# Schema_linksonder.net
KiCad netlist of a schematic drawn in Altium Designer
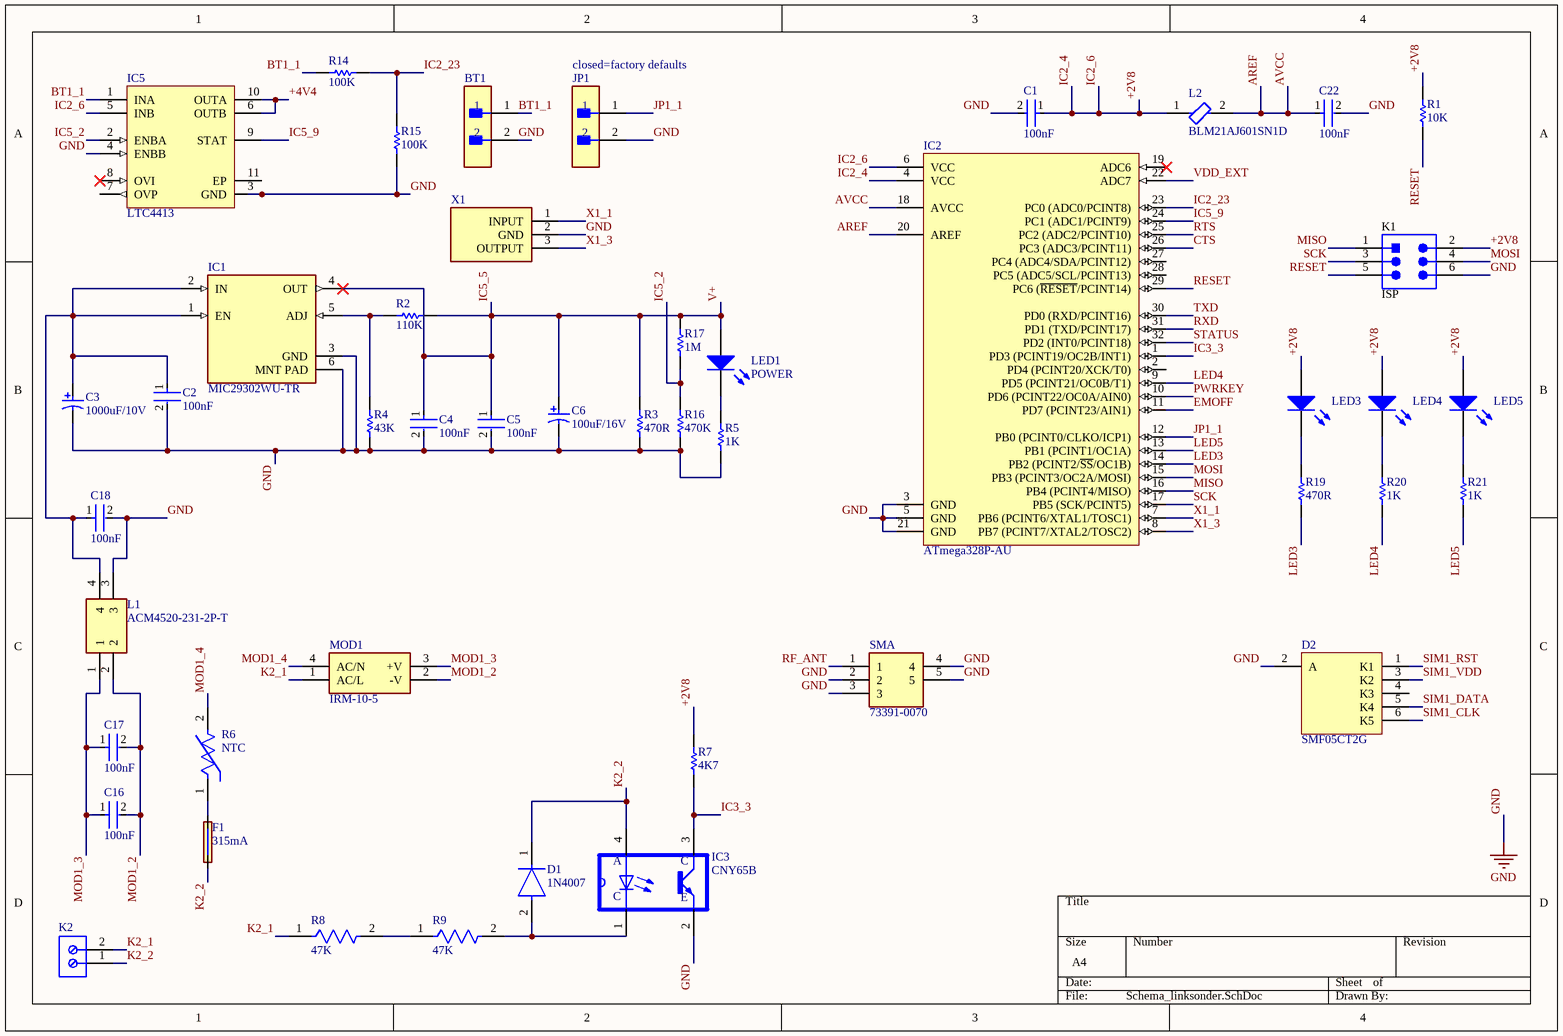
[diagram p0: Schema_linksonder.SchDoc]

(export (version "E")
  (design (tool "Eeschema 10.0.6"))
  (components
    (comp (ref "BT1")
      (value "~")
      (footprint "FP-M20-9990246-MFG")
      (description "CONN HEADER VERT 2POS 2.54MM")
      (fields
        (field (name "OCTOPART") "https://octopart.com/m20-9990246-harwin-2590635")
        (field (name "MANUFACTURER") "Harwin")
      )
      (libsource (lib "Altium Content Vault") (part "3bc925449376181038e59eaffc5286c"))
    )
    (comp (ref "C1")
      (value "100nF")
      (footprint "FP-CC1206-1_25-MFG")
      (description "CAP CER 0.1UF 50V X7R 1206")
      (fields
        (field (name "OCTOPART") "https://octopart.com/cc1206krx7r9bb104-yageo-39467816")
        (field (name "TOLERANCE") "0.1")
      )
      (libsource (lib "Altium Content Vault") (part "11868f565c42a9108669ba33697ecf6"))
    )
    (comp (ref "C2")
      (value "100nF")
      (footprint "FP-CC1206-1_25-MFG")
      (description "CAP CER 0.1UF 50V X7R 1206")
      (fields
        (field (name "OCTOPART") "https://octopart.com/cc1206krx7r9bb104-yageo-39467816")
        (field (name "TOLERANCE") "0.1")
      )
      (libsource (lib "Altium Content Vault") (part "11868f565c42a9108669ba33697ecf6"))
    )
    (comp (ref "C3")
      (value "1000uF/10V")
      (footprint "NIC-CAPA2-10X10_V")
      (fields (field (name "MANUFACTURER") "Nichicon") (field (name "PARTNUMBER") "UUD1A102MNL1GS"))
      (libsource (lib "Altium Content Vault") (part "NIC-CAP-P-2"))
    )
    (comp (ref "C4")
      (value "100nF")
      (footprint "FP-CC1206-1_25-MFG")
      (description "CAP CER 0.1UF 50V X7R 1206")
      (fields
        (field (name "OCTOPART") "https://octopart.com/cc1206krx7r9bb104-yageo-39467816")
        (field (name "TOLERANCE") "0.1")
      )
      (libsource (lib "Altium Content Vault") (part "11868f565c42a9108669ba33697ecf6"))
    )
    (comp (ref "C5")
      (value "100nF")
      (footprint "FP-CC1206-1_25-MFG")
      (description "CAP CER 0.1UF 50V X7R 1206")
      (fields
        (field (name "OCTOPART") "https://octopart.com/cc1206krx7r9bb104-yageo-39467816")
        (field (name "TOLERANCE") "0.1")
      )
      (libsource (lib "Altium Content Vault") (part "11868f565c42a9108669ba33697ecf6"))
    )
    (comp (ref "C6")
      (value "100uF/16V")
      (footprint "AVX-TAJ-C-2_M")
      (description "Standard Tantalum, 100 uF, +/- 10%, 16 V, -55 to 125 degC, 2-Pin SMD (2312), RoHS, Tape and Reel")
      (fields (field (name "TOLERANCE") "10%") (field (name "MANUFACTURER") "AVX"))
      (libsource (lib "Altium Content Vault") (part "CAP-P-2"))
    )
    (comp (ref "C16")
      (value "100nF")
      (footprint "FP-CC1206-1_25-MFG")
      (description "CAP CER 0.1UF 50V X7R 1206")
      (fields
        (field (name "OCTOPART") "https://octopart.com/cc1206krx7r9bb104-yageo-39467816")
        (field (name "TOLERANCE") "0.1")
      )
      (libsource (lib "Altium Content Vault") (part "11868f565c42a9108669ba33697ecf6"))
    )
    (comp (ref "C17")
      (value "100nF")
      (footprint "FP-CC1206-1_25-MFG")
      (description "CAP CER 0.1UF 50V X7R 1206")
      (fields
        (field (name "OCTOPART") "https://octopart.com/cc1206krx7r9bb104-yageo-39467816")
        (field (name "TOLERANCE") "0.1")
      )
      (libsource (lib "Altium Content Vault") (part "11868f565c42a9108669ba33697ecf6"))
    )
    (comp (ref "C18")
      (value "100nF")
      (footprint "FP-CC1206-1_25-MFG")
      (description "CAP CER 0.1UF 50V X7R 1206")
      (fields
        (field (name "OCTOPART") "https://octopart.com/cc1206krx7r9bb104-yageo-39467816")
        (field (name "TOLERANCE") "0.1")
      )
      (libsource (lib "Altium Content Vault") (part "11868f565c42a9108669ba33697ecf6"))
    )
    (comp (ref "C22")
      (value "100nF")
      (footprint "FP-CC1206-1_25-MFG")
      (description "CAP CER 0.1UF 50V X7R 1206")
      (fields
        (field (name "OCTOPART") "https://octopart.com/cc1206krx7r9bb104-yageo-39467816")
        (field (name "TOLERANCE") "0.1")
      )
      (libsource (lib "Altium Content Vault") (part "11868f565c42a9108669ba33697ecf6"))
    )
    (comp (ref "D1")
      (value "1N4007")
      (footprint "FP-1N4007-MFG")
      (description "DIODE GEN PURP 1KV 1A DO204AL")
      (fields
        (field (name "OCTOPART") "https://octopart.com/1n4007-e3%2F54-vishay-39548207")
        (field (name "MANUFACTURER") "Vishay")
      )
      (libsource (lib "Altium Content Vault") (part "d7152d700b627762746794eb795d46e"))
    )
    (comp (ref "D2")
      (value "SMF05CT2G")
      (footprint "ONSC-SC70-6-419B-02_W_V")
      (description "5-Line Transient Voltage Suppressor Array, 6-Pin SC70, Pb-Free, Tape and Reel")
      (fields (field (name "MANUFACTURER") "On Semiconductor"))
      (libsource (lib "Altium Content Vault") (part "ONSC-K1A2K3K4K5K6-6"))
    )
    (comp (ref "F1")
      (value "315mA")
      (footprint "MC000827")
      (description "Fuse Holder, 250 V, 6.3 A, Pcb Fuse Holder, Through Hole, 1")
      (fields (field (name "MF") "Multicomp") (field (name "MP") "MC000827"))
      (libsource (lib "MC000827") (part "MC000827"))
    )
    (comp (ref "IC1")
      (value "MIC29302WU-TR")
      (footprint "FP-C04-012-MFG")
      (description "IC REG LINEAR POS ADJ 3A TO263-5")
      (fields
        (field (name "MANUFACTURER") "Microchip")
        (field (name "OCTOPART") "https://octopart.com/mic29302wu-tr-microchip-66801318")
      )
      (libsource (lib "Altium Content Vault") (part "0db40f55fda0e91d0d14528974a446d"))
    )
    (comp (ref "IC2")
      (value "ATmega328P-AU")
      (footprint "32A_M")
      (libsource (lib "Altium Content Vault") (part "MC-8B-ATM48-SQ32"))
    )
    (comp (ref "IC3")
      (value "CNY65B")
      (footprint "DIP762W50P1524L1780H610Q4")
      (libsource (lib "CNY65B") (part "CNY65B"))
    )
    (comp (ref "IC5")
      (value "LTC4413")
      (footprint "LT-DD-10_V")
      (fields
        (field (name "MANUFACTURER") "Linear Technology")
        (field (name "PARTNUMBER") "LTC4413EDD-2#PBF")
      )
      (libsource (lib "Altium Content Vault") (part "LT-LTC4413-2-DD-10"))
    )
    (comp (ref "JP1")
      (value "closed=factory defaults")
      (footprint "FP-M20-9990246-MFG")
      (description "CONN HEADER VERT 2POS 2.54MM")
      (fields
        (field (name "OCTOPART") "https://octopart.com/m20-9990246-harwin-2590635")
        (field (name "MANUFACTURER") "Harwin")
      )
      (libsource (lib "Altium Content Vault") (part "3bc925449376181038e59eaffc5286c"))
    )
    (comp (ref "K1")
      (value "ISP")
      (footprint "SMTC-TSW-103-08-L-D_V")
      (fields (field (name "MANUFACTURER") "Samtec"))
      (libsource (lib "Altium Content Vault") (part "CN-2P-M-R6"))
    )
    (comp (ref "K2")
      (value "~")
      (footprint "PHOE-1714955_V")
      (description "PC Terminal Block, Pitch 6.35 mm, 1 x 2 Position, Height 21.5 mm, Tail Lenght 5.1 mm, RoHS, Bulk")
      (fields (field (name "MANUFACTURER") "Phoenix Contact"))
      (libsource (lib "Altium Content Vault") (part "CN-1P-F-TB2"))
    )
    (comp (ref "L1")
      (value "ACM4520-231-2P-T")
      (footprint "SamacSys:ACM4520")
      (description "Filter")
      (fields
        (field (name "RS PART NUMBER") "9164134P")
        (field (name "MANUFACTURER_PART_NUMBER") "ACM4520-231-2P-T000")
      )
      (libsource (lib "*") (part "ACM4520-231-2P-T000"))
    )
    (comp (ref "L2")
      (value "BLM21AJ601SN1D")
      (footprint "FP-BLM21-0_2-t0_85-e0_5-MFG")
      (description "Chip Ferrite Bead, 0805, 22Ω @ 100MHz, 0.009Ω, 25%, 6A")
      (fields (field (name "TOLERANCE") "25%"))
      (libsource (lib "Altium Content Vault") (part "5f30dd21d616792df468990f7003faa"))
    )
    (comp (ref "LED1")
      (value "POWER")
      (footprint "1206_A")
      (description "SMD mono-color Chip LED, WL-SMCW, Yellow")
      (fields (field (name "PARTNUMBER") "150120YS75000") (field (name "MANUFACTURER") "Wuerth Elektronik"))
      (libsource (lib "Altium Content Vault") (part "WE-LED_K1A2-2"))
    )
    (comp (ref "LED3")
      (value "~")
      (footprint "1206_A")
      (description "SMD mono-color Chip LED, WL-SMCW, Green")
      (fields (field (name "MANUFACTURER") "Wuerth Elektronik") (field (name "PARTNUMBER") "150120GS75000"))
      (libsource (lib "Altium Content Vault") (part "WE-LED_K1A2-2"))
    )
    (comp (ref "LED4")
      (value "~")
      (footprint "1206_A")
      (description "SMD mono-color Chip LED, WL-SMCW, Green")
      (fields (field (name "MANUFACTURER") "Wuerth Elektronik") (field (name "PARTNUMBER") "150120GS75000"))
      (libsource (lib "Altium Content Vault") (part "WE-LED_K1A2-2"))
    )
    (comp (ref "LED5")
      (value "~")
      (footprint "1206_A")
      (description "SMD mono-color Chip LED, WL-SMCW, Green")
      (fields (field (name "MANUFACTURER") "Wuerth Elektronik") (field (name "PARTNUMBER") "150120GS75000"))
      (libsource (lib "Altium Content Vault") (part "WE-LED_K1A2-2"))
    )
    (comp (ref "MOD1")
      (value "IRM-10-5")
      (footprint "SamacSys:IRM-10")
      (description "Power Supply")
      (fields (field (name "MOUSER PART NUMBER") "709-IRM10-5"))
      (libsource (lib "IRM-10-5") (part "IRM-10-5"))
    )
    (comp (ref "R1")
      (value "10K")
      (footprint "RESC3225X70X50NL20T20")
      (fields (field (name "MANUFACTURER") "Panasonic") (field (name "PART NUMBER") "ERJ14BQF3R3U"))
      (libsource (lib "Altium Content Vault") (part "RES"))
    )
    (comp (ref "R2")
      (value "110K")
      (footprint "RESC3225X70X50NL20T20")
      (fields (field (name "MANUFACTURER") "Panasonic") (field (name "PART NUMBER") "ERJ14BQF3R3U"))
      (libsource (lib "Altium Content Vault") (part "RES"))
    )
    (comp (ref "R3")
      (value "470R")
      (footprint "RESC3225X70X50NL20T20")
      (fields (field (name "MANUFACTURER") "Panasonic") (field (name "PART NUMBER") "ERJ14BQF3R3U"))
      (libsource (lib "Altium Content Vault") (part "RES"))
    )
    (comp (ref "R4")
      (value "43K")
      (footprint "RESC3225X70X50NL20T20")
      (fields (field (name "MANUFACTURER") "Panasonic") (field (name "PART NUMBER") "ERJ14BQF3R3U"))
      (libsource (lib "Altium Content Vault") (part "RES"))
    )
    (comp (ref "R5")
      (value "1K")
      (footprint "RESC3225X70X50NL20T20")
      (fields (field (name "MANUFACTURER") "Panasonic") (field (name "PART NUMBER") "ERJ14BQF3R3U"))
      (libsource (lib "Altium Content Vault") (part "RES"))
    )
    (comp (ref "R6")
      (value "NTC")
      (footprint "FP-NTPAA-MFG")
      (description "ICL 5.1 OHM 15% 2.5A 10MM")
      (fields (field (name "TOLERANCE") "15%") (field (name "VOLTAGE") "264V"))
      (libsource (lib "Altium Content Vault") (part "3b148a6ebabc5fb4d708a66c052d352"))
    )
    (comp (ref "R7")
      (value "4K7")
      (footprint "RESC3225X70X50NL20T20")
      (fields (field (name "MANUFACTURER") "Panasonic") (field (name "PART NUMBER") "ERJ14BQF3R3U"))
      (libsource (lib "Altium Content Vault") (part "RES"))
    )
    (comp (ref "R8")
      (value "47K")
      (footprint "FP-MRS25-MFG")
      (description "RES 1.1K OHM 0.6W 1% AXIAL")
      (fields
        (field (name "MANUFACTURER") "Vishay BC Components")
        (field (name "OCTOPART") "https://octopart.com/mrs25000c1101fct00-vishay-43740214")
      )
      (libsource (lib "Altium Content Vault") (part "1029c3af85768c4190bb7ad29bc67b5"))
    )
    (comp (ref "R9")
      (value "47K")
      (footprint "FP-MRS25-MFG")
      (description "RES 1.1K OHM 0.6W 1% AXIAL")
      (fields
        (field (name "MANUFACTURER") "Vishay BC Components")
        (field (name "OCTOPART") "https://octopart.com/mrs25000c1101fct00-vishay-43740214")
      )
      (libsource (lib "Altium Content Vault") (part "1029c3af85768c4190bb7ad29bc67b5"))
    )
    (comp (ref "R14")
      (value "100K")
      (footprint "RESC3225X70X50NL20T20")
      (fields (field (name "MANUFACTURER") "Panasonic") (field (name "PART NUMBER") "ERJ14BQF3R3U"))
      (libsource (lib "Altium Content Vault") (part "RES"))
    )
    (comp (ref "R15")
      (value "100K")
      (footprint "RESC3225X70X50NL20T20")
      (fields (field (name "MANUFACTURER") "Panasonic") (field (name "PART NUMBER") "ERJ14BQF3R3U"))
      (libsource (lib "Altium Content Vault") (part "RES"))
    )
    (comp (ref "R16")
      (value "470K")
      (footprint "RESC3225X70X50NL20T20")
      (fields (field (name "MANUFACTURER") "Panasonic") (field (name "PART NUMBER") "ERJ14BQF3R3U"))
      (libsource (lib "Altium Content Vault") (part "RES"))
    )
    (comp (ref "R17")
      (value "1M")
      (footprint "RESC3225X70X50NL20T20")
      (fields (field (name "MANUFACTURER") "Panasonic") (field (name "PART NUMBER") "ERJ14BQF3R3U"))
      (libsource (lib "Altium Content Vault") (part "RES"))
    )
    (comp (ref "R19")
      (value "470R")
      (footprint "RESC3225X70X50NL20T20")
      (fields (field (name "MANUFACTURER") "Panasonic") (field (name "PART NUMBER") "ERJ14BQF3R3U"))
      (libsource (lib "Altium Content Vault") (part "RES"))
    )
    (comp (ref "R20")
      (value "1K")
      (footprint "RESC3225X70X50NL20T20")
      (fields (field (name "MANUFACTURER") "Panasonic") (field (name "PART NUMBER") "ERJ14BQF3R3U"))
      (libsource (lib "Altium Content Vault") (part "RES"))
    )
    (comp (ref "R21")
      (value "1K")
      (footprint "RESC3225X70X50NL20T20")
      (fields (field (name "MANUFACTURER") "Panasonic") (field (name "PART NUMBER") "ERJ14BQF3R3U"))
      (libsource (lib "Altium Content Vault") (part "RES"))
    )
    (comp (ref "SMA")
      (value "73391-0070")
      (footprint "SamacSys:733910070")
      (description "Connector")
      (fields (field (name "MOUSER PART NUMBER") "538-73391-0070"))
      (libsource (lib "Molex 73391-0070") (part "73391-0070"))
    )
    (comp (ref "X1")
      (value "~")
      (footprint "SamacSys:CSTCC8M00G53R0")
      (description "Crystal or Oscillator")
      (fields
        (field (name "MANUFACTURER_PART_NUMBER") "CSTCC8M00G53-R0")
        (field (name "MOUSER PART NUMBER") "81-CSTCC8.00MG-TC")
      )
      (libsource (lib "*") (part "CSTCC8M00G53-R0"))
    )
  )
  (nets
    (net (code "1") (name "/+2V8") (class "Default")
      (node (ref "C1") (pin "1") (pinfunction "1_1") (pintype "passive"))
      (node (ref "IC2") (pin "4") (pinfunction "VCC_4") (pintype "power_in"))
      (node (ref "IC2") (pin "6") (pinfunction "VCC_6") (pintype "power_in"))
      (node (ref "IC5") (pin "5") (pinfunction "INB_5") (pintype "power_in"))
      (node (ref "K1") (pin "2") (pinfunction "2_2") (pintype "passive"))
      (node (ref "L2") (pin "1") (pinfunction "1_1") (pintype "passive"))
      (node (ref "LED3") (pin "2") (pinfunction "A_2") (pintype "passive"))
      (node (ref "LED4") (pin "2") (pinfunction "A_2") (pintype "passive"))
      (node (ref "LED5") (pin "2") (pinfunction "A_2") (pintype "passive"))
      (node (ref "R1") (pin "2") (pinfunction "2_2") (pintype "passive"))
      (node (ref "R7") (pin "2") (pinfunction "2_2") (pintype "passive"))
    )
    (net (code "2") (name "/+4V4") (class "Default")
      (node (ref "IC5") (pin "10") (pinfunction "OUTA_10") (pintype "power_in"))
      (node (ref "IC5") (pin "6") (pinfunction "OUTB_6") (pintype "power_in"))
    )
    (net (code "3") (name "/AREF") (class "Default")
      (node (ref "C22") (pin "1") (pinfunction "1_1") (pintype "passive"))
      (node (ref "IC2") (pin "18") (pinfunction "AVCC_18") (pintype "power_in"))
      (node (ref "IC2") (pin "20") (pinfunction "AREF_20") (pintype "passive"))
      (node (ref "L2") (pin "2") (pinfunction "2_2") (pintype "passive"))
    )
    (net (code "4") (name "/BT1_1") (class "Default")
      (node (ref "BT1") (pin "1") (pinfunction "1_1") (pintype "passive"))
      (node (ref "IC5") (pin "1") (pinfunction "INA_1") (pintype "power_in"))
      (node (ref "R14") (pin "1") (pinfunction "1_1") (pintype "passive"))
    )
    (net (code "5") (name "/CTS") (class "Default")
      (node (ref "IC2") (pin "26") (pinfunction "PC3_(ADC3/PCINT11)_26") (pintype "bidirectional"))
    )
    (net (code "6") (name "/EMOFF") (class "Default")
      (node (ref "IC2") (pin "11") (pinfunction "PD7_(PCINT23/AIN1)_11") (pintype "bidirectional"))
    )
    (net (code "7") (name "/IC2_23") (class "Default")
      (node (ref "IC2") (pin "23") (pinfunction "PC0_(ADC0/PCINT8)_23") (pintype "bidirectional"))
      (node (ref "R14") (pin "2") (pinfunction "2_2") (pintype "passive"))
      (node (ref "R15") (pin "2") (pinfunction "2_2") (pintype "passive"))
    )
    (net (code "8") (name "/IC3_3") (class "Default")
      (node (ref "IC2") (pin "1") (pinfunction "PD3_(PCINT19/OC2B/INT1)_1") (pintype "bidirectional"))
      (node (ref "IC3") (pin "3") (pinfunction "C`_3") (pintype "passive"))
      (node (ref "R7") (pin "1") (pinfunction "1_1") (pintype "passive"))
    )
    (net (code "9") (name "/IC5_2") (class "Default")
      (node (ref "IC5") (pin "2") (pinfunction "ENBA_2") (pintype "input"))
      (node (ref "R16") (pin "2") (pinfunction "2_2") (pintype "passive"))
      (node (ref "R17") (pin "1") (pinfunction "1_1") (pintype "passive"))
    )
    (net (code "10") (name "/IC5_5") (class "Default")
      (node (ref "C4") (pin "1") (pinfunction "1_1") (pintype "passive"))
      (node (ref "C5") (pin "1") (pinfunction "1_1") (pintype "passive"))
      (node (ref "C6") (pin "1") (pinfunction "1_1") (pintype "passive"))
      (node (ref "IC1") (pin "4") (pinfunction "OUT_4") (pintype "output"))
      (node (ref "LED1") (pin "2") (pinfunction "A_2") (pintype "passive"))
      (node (ref "R17") (pin "2") (pinfunction "2_2") (pintype "passive"))
      (node (ref "R2") (pin "1") (pinfunction "1_1") (pintype "passive"))
      (node (ref "R3") (pin "2") (pinfunction "2_2") (pintype "passive"))
    )
    (net (code "11") (name "/IC5_9") (class "Default")
      (node (ref "IC2") (pin "24") (pinfunction "PC1_(ADC1/PCINT9)_24") (pintype "bidirectional"))
      (node (ref "IC5") (pin "9") (pinfunction "STAT_9") (pintype "open_collector"))
    )
    (net (code "12") (name "/JP1_1") (class "Default")
      (node (ref "IC2") (pin "12") (pinfunction "PB0_(PCINT0/CLKO/ICP1)_12") (pintype "bidirectional"))
      (node (ref "JP1") (pin "1") (pinfunction "1_1") (pintype "passive"))
    )
    (net (code "13") (name "/K2_1") (class "Default")
      (node (ref "K2") (pin "2") (pinfunction "2_2") (pintype "passive"))
      (node (ref "MOD1") (pin "1") (pinfunction "AC/L_1") (pintype "passive"))
      (node (ref "R8") (pin "1") (pinfunction "1_1") (pintype "passive"))
    )
    (net (code "14") (name "/K2_2") (class "Default")
      (node (ref "D1") (pin "1") (pinfunction "C_1") (pintype "passive"))
      (node (ref "F1") (pin "P$2") (pinfunction "2_P$2") (pintype "passive"))
      (node (ref "IC3") (pin "4") (pinfunction "A_4") (pintype "passive"))
      (node (ref "K2") (pin "1") (pinfunction "1_1") (pintype "passive"))
    )
    (net (code "15") (name "/LED3") (class "Default")
      (node (ref "IC2") (pin "14") (pinfunction "PB2_(PCINT2/~{SS}/OC1B)_14") (pintype "bidirectional"))
      (node (ref "R19") (pin "1") (pinfunction "1_1") (pintype "passive"))
    )
    (net (code "16") (name "/LED4") (class "Default")
      (node (ref "IC2") (pin "9") (pinfunction "PD5_(PCINT21/OC0B/T1)_9") (pintype "bidirectional"))
      (node (ref "R20") (pin "1") (pinfunction "1_1") (pintype "passive"))
    )
    (net (code "17") (name "/LED5") (class "Default")
      (node (ref "IC2") (pin "13") (pinfunction "PB1_(PCINT1/OC1A)_13") (pintype "bidirectional"))
      (node (ref "R21") (pin "1") (pinfunction "1_1") (pintype "passive"))
    )
    (net (code "18") (name "/MISO") (class "Default")
      (node (ref "IC2") (pin "16") (pinfunction "PB4_(PCINT4/MISO)_16") (pintype "bidirectional"))
      (node (ref "K1") (pin "1") (pinfunction "1_1") (pintype "passive"))
    )
    (net (code "19") (name "/MOD1_2") (class "Default")
      (node (ref "C16") (pin "2") (pinfunction "2_2") (pintype "passive"))
      (node (ref "C17") (pin "2") (pinfunction "2_2") (pintype "passive"))
      (node (ref "L1") (pin "2") (pinfunction "2_2") (pintype "passive"))
      (node (ref "MOD1") (pin "2") (pinfunction "-V_2") (pintype "passive"))
    )
    (net (code "20") (name "/MOD1_3") (class "Default")
      (node (ref "C16") (pin "1") (pinfunction "1_1") (pintype "passive"))
      (node (ref "C17") (pin "1") (pinfunction "1_1") (pintype "passive"))
      (node (ref "L1") (pin "1") (pinfunction "1_1") (pintype "passive"))
      (node (ref "MOD1") (pin "3") (pinfunction "+V_3") (pintype "passive"))
    )
    (net (code "21") (name "/MOD1_4") (class "Default")
      (node (ref "MOD1") (pin "4") (pinfunction "AC/N_4") (pintype "passive"))
      (node (ref "R6") (pin "2") (pinfunction "2_2") (pintype "passive"))
    )
    (net (code "22") (name "/MOSI") (class "Default")
      (node (ref "IC2") (pin "15") (pinfunction "PB3_(PCINT3/OC2A/MOSI)_15") (pintype "bidirectional"))
      (node (ref "K1") (pin "4") (pinfunction "4_4") (pintype "passive"))
    )
    (net (code "23") (name "/PWRKEY") (class "Default")
      (node (ref "IC2") (pin "10") (pinfunction "PD6_(PCINT22/OC0A/AIN0)_10") (pintype "bidirectional"))
    )
    (net (code "24") (name "/RESET") (class "Default")
      (node (ref "IC2") (pin "29") (pinfunction "PC6_(~{RESET}/PCINT14)_29") (pintype "bidirectional"))
      (node (ref "K1") (pin "5") (pinfunction "5_5") (pintype "passive"))
      (node (ref "R1") (pin "1") (pinfunction "1_1") (pintype "passive"))
    )
    (net (code "25") (name "/RF_ANT") (class "Default")
      (node (ref "SMA") (pin "1") (pinfunction "1_1") (pintype "passive"))
    )
    (net (code "26") (name "/RTS") (class "Default")
      (node (ref "IC2") (pin "25") (pinfunction "PC2_(ADC2/PCINT10)_25") (pintype "bidirectional"))
    )
    (net (code "27") (name "/RXD") (class "Default")
      (node (ref "IC2") (pin "31") (pinfunction "PD1_(TXD/PCINT17)_31") (pintype "bidirectional"))
    )
    (net (code "28") (name "/SCK") (class "Default")
      (node (ref "IC2") (pin "17") (pinfunction "PB5_(SCK/PCINT5)_17") (pintype "bidirectional"))
      (node (ref "K1") (pin "3") (pinfunction "3_3") (pintype "passive"))
    )
    (net (code "29") (name "/SIM1_CLK") (class "Default")
      (node (ref "D2") (pin "6") (pinfunction "K5_6") (pintype "passive"))
    )
    (net (code "30") (name "/SIM1_DATA") (class "Default")
      (node (ref "D2") (pin "5") (pinfunction "K4_5") (pintype "passive"))
    )
    (net (code "31") (name "/SIM1_RST") (class "Default")
      (node (ref "D2") (pin "1") (pinfunction "K1_1") (pintype "passive"))
    )
    (net (code "32") (name "/SIM1_VDD") (class "Default")
      (node (ref "D2") (pin "3") (pinfunction "K2_3") (pintype "passive"))
    )
    (net (code "33") (name "/STATUS") (class "Default")
      (node (ref "IC2") (pin "32") (pinfunction "PD2_(INT0/PCINT18)_32") (pintype "bidirectional"))
    )
    (net (code "34") (name "/TXD") (class "Default")
      (node (ref "IC2") (pin "30") (pinfunction "PD0_(RXD/PCINT16)_30") (pintype "bidirectional"))
    )
    (net (code "35") (name "/VDD_EXT") (class "Default")
      (node (ref "IC2") (pin "22") (pinfunction "ADC7_22") (pintype "input"))
    )
    (net (code "36") (name "/X1_1") (class "Default")
      (node (ref "IC2") (pin "7") (pinfunction "PB6_(PCINT6/XTAL1/TOSC1)_7") (pintype "bidirectional"))
      (node (ref "X1") (pin "1") (pinfunction "INPUT_1") (pintype "passive"))
    )
    (net (code "37") (name "/X1_3") (class "Default")
      (node (ref "IC2") (pin "8") (pinfunction "PB7_(PCINT7/XTAL2/TOSC2)_8") (pintype "bidirectional"))
      (node (ref "X1") (pin "3") (pinfunction "OUTPUT_3") (pintype "passive"))
    )
    (net (code "38") (name "GND") (class "Default")
      (node (ref "BT1") (pin "2") (pinfunction "2_2") (pintype "passive"))
      (node (ref "C1") (pin "2") (pinfunction "2_2") (pintype "passive"))
      (node (ref "C18") (pin "2") (pinfunction "2_2") (pintype "passive"))
      (node (ref "C2") (pin "2") (pinfunction "2_2") (pintype "passive"))
      (node (ref "C22") (pin "2") (pinfunction "2_2") (pintype "passive"))
      (node (ref "C3") (pin "2") (pinfunction "2_2") (pintype "passive"))
      (node (ref "C4") (pin "2") (pinfunction "2_2") (pintype "passive"))
      (node (ref "C5") (pin "2") (pinfunction "2_2") (pintype "passive"))
      (node (ref "C6") (pin "2") (pinfunction "2_2") (pintype "passive"))
      (node (ref "D2") (pin "2") (pinfunction "A_2") (pintype "passive"))
      (node (ref "IC1") (pin "3") (pinfunction "GND_3") (pintype "power_in"))
      (node (ref "IC1") (pin "6") (pinfunction "MNT_PAD_6") (pintype "passive"))
      (node (ref "IC2") (pin "21") (pinfunction "GND_21") (pintype "power_in"))
      (node (ref "IC2") (pin "3") (pinfunction "GND_3") (pintype "power_in"))
      (node (ref "IC2") (pin "5") (pinfunction "GND_5") (pintype "power_in"))
      (node (ref "IC3") (pin "2") (pinfunction "E_2") (pintype "passive"))
      (node (ref "IC5") (pin "3") (pinfunction "GND_3") (pintype "power_in"))
      (node (ref "IC5") (pin "4") (pinfunction "ENBB_4") (pintype "input"))
      (node (ref "JP1") (pin "2") (pinfunction "2_2") (pintype "passive"))
      (node (ref "K1") (pin "6") (pinfunction "6_6") (pintype "passive"))
      (node (ref "L1") (pin "3") (pinfunction "3_3") (pintype "passive"))
      (node (ref "R15") (pin "1") (pinfunction "1_1") (pintype "passive"))
      (node (ref "R16") (pin "1") (pinfunction "1_1") (pintype "passive"))
      (node (ref "R3") (pin "1") (pinfunction "1_1") (pintype "passive"))
      (node (ref "R4") (pin "1") (pinfunction "1_1") (pintype "passive"))
      (node (ref "R5") (pin "1") (pinfunction "1_1") (pintype "passive"))
      (node (ref "SMA") (pin "2") (pinfunction "2_2") (pintype "passive"))
      (node (ref "SMA") (pin "3") (pinfunction "3_3") (pintype "passive"))
      (node (ref "SMA") (pin "4") (pinfunction "4_4") (pintype "passive"))
      (node (ref "SMA") (pin "5") (pinfunction "5_5") (pintype "passive"))
      (node (ref "X1") (pin "2") (pinfunction "GND_2") (pintype "passive"))
    )
    (net (code "39") (name "Net-(D1-A)") (class "Default")
      (node (ref "D1") (pin "2") (pinfunction "A_2") (pintype "passive"))
      (node (ref "IC3") (pin "1") (pinfunction "C_1") (pintype "passive"))
      (node (ref "R9") (pin "2") (pinfunction "2_2") (pintype "passive"))
    )
    (net (code "40") (name "Net-(F1-1)") (class "Default")
      (node (ref "F1") (pin "P$1") (pinfunction "1_P$1") (pintype "passive"))
      (node (ref "R6") (pin "1") (pinfunction "1_1") (pintype "passive"))
    )
    (net (code "41") (name "Net-(IC1-ADJ)") (class "Default")
      (node (ref "IC1") (pin "5") (pinfunction "ADJ_5") (pintype "input"))
      (node (ref "R2") (pin "2") (pinfunction "2_2") (pintype "passive"))
      (node (ref "R4") (pin "2") (pinfunction "2_2") (pintype "passive"))
    )
    (net (code "42") (name "Net-(IC1-EN)") (class "Default")
      (node (ref "C18") (pin "1") (pinfunction "1_1") (pintype "passive"))
      (node (ref "C2") (pin "1") (pinfunction "1_1") (pintype "passive"))
      (node (ref "C3") (pin "1") (pinfunction "1_1") (pintype "passive"))
      (node (ref "IC1") (pin "1") (pinfunction "EN_1") (pintype "input"))
      (node (ref "IC1") (pin "2") (pinfunction "IN_2") (pintype "input"))
      (node (ref "L1") (pin "4") (pinfunction "4_4") (pintype "passive"))
    )
    (net (code "43") (name "Net-(LED1-K)") (class "Default")
      (node (ref "LED1") (pin "1") (pinfunction "K_1") (pintype "passive"))
      (node (ref "R5") (pin "2") (pinfunction "2_2") (pintype "passive"))
    )
    (net (code "44") (name "Net-(LED3-K)") (class "Default")
      (node (ref "LED3") (pin "1") (pinfunction "K_1") (pintype "passive"))
      (node (ref "R19") (pin "2") (pinfunction "2_2") (pintype "passive"))
    )
    (net (code "45") (name "Net-(LED4-K)") (class "Default")
      (node (ref "LED4") (pin "1") (pinfunction "K_1") (pintype "passive"))
      (node (ref "R20") (pin "2") (pinfunction "2_2") (pintype "passive"))
    )
    (net (code "46") (name "Net-(LED5-K)") (class "Default")
      (node (ref "LED5") (pin "1") (pinfunction "K_1") (pintype "passive"))
      (node (ref "R21") (pin "2") (pinfunction "2_2") (pintype "passive"))
    )
    (net (code "47") (name "Net-(R8-Pad2)") (class "Default")
      (node (ref "R8") (pin "2") (pinfunction "2_2") (pintype "passive"))
      (node (ref "R9") (pin "1") (pinfunction "1_1") (pintype "passive"))
    )
    (net (code "48") (name "unconnected-(D2-K3-Pad4)") (class "Default")
      (node (ref "D2") (pin "4") (pinfunction "K3_4") (pintype "passive"))
    )
    (net (code "49") (name "unconnected-(IC2-ADC6-Pad19)") (class "Default")
      (node (ref "IC2") (pin "19") (pinfunction "ADC6_19") (pintype "input+no_connect"))
    )
    (net (code "50") (name "unconnected-(IC2-PC4_(ADC4{slash}SDA{slash}PCINT12)-Pad27)") (class "Default")
      (node (ref "IC2") (pin "27") (pinfunction "PC4_(ADC4/SDA/PCINT12)_27") (pintype "bidirectional"))
    )
    (net (code "51") (name "unconnected-(IC2-PC5_(ADC5{slash}SCL{slash}PCINT13)-Pad28)") (class "Default")
      (node (ref "IC2") (pin "28") (pinfunction "PC5_(ADC5/SCL/PCINT13)_28") (pintype "bidirectional"))
    )
    (net (code "52") (name "unconnected-(IC2-PD4_(PCINT20{slash}XCK{slash}T0)-Pad2)") (class "Default")
      (node (ref "IC2") (pin "2") (pinfunction "PD4_(PCINT20/XCK/T0)_2") (pintype "bidirectional"))
    )
    (net (code "53") (name "unconnected-(IC5-EP-Pad11)") (class "Default")
      (node (ref "IC5") (pin "11") (pinfunction "EP_11") (pintype "power_in"))
    )
    (net (code "54") (name "unconnected-(IC5-OVI-Pad8)") (class "Default")
      (node (ref "IC5") (pin "8") (pinfunction "OVI_8") (pintype "input+no_connect"))
    )
    (net (code "55") (name "unconnected-(IC5-OVP-Pad7)") (class "Default")
      (node (ref "IC5") (pin "7") (pinfunction "OVP_7") (pintype "output"))
    )
  )
)
